# Power_grad2.net
KiCad netlist of a schematic drawn in EAGLE
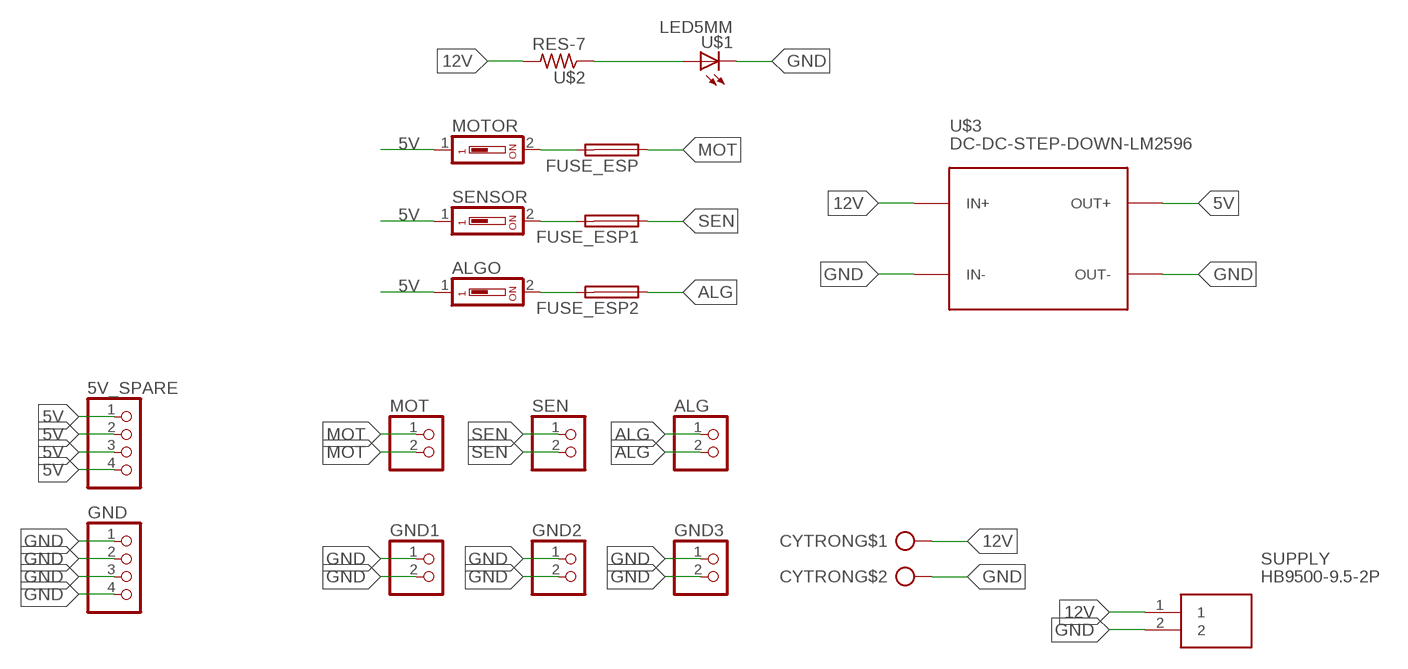
[diagram p0: schematic, sheet 1]

(export (version "E")
  (design (tool "Eeschema 10.0.6"))
  (components
    (comp (ref "5V_SPARE")
      (value "PINHD-1X4")
      (footprint "eagle-import:1X04")
      (libsource (lib "eagle-import") (part "PINHD-1X4"))
    )
    (comp (ref "ALG")
      (value "PINHD-2_DATA")
      (footprint "eagle-import:1X02_DATA")
      (libsource (lib "eagle-import") (part "PINHD-2_DATA"))
    )
    (comp (ref "ALGO")
      (value "DS01")
      (footprint "eagle-import:DS-01")
      (libsource (lib "eagle-import") (part "DS01"))
    )
    (comp (ref "CYTRON")
      (value "CON_PTR_2")
      (footprint "eagle-import:AK300_2")
      (libsource (lib "eagle-import") (part "CON_PTR_2"))
    )
    (comp (ref "FUSE_ESP")
      (value "FUSE_HOLDER")
      (footprint "eagle-import:SH22,5A")
      (libsource (lib "eagle-import") (part "FUSE_HOLDER"))
    )
    (comp (ref "FUSE_ESP1")
      (value "FUSE_HOLDER")
      (footprint "eagle-import:SH22,5A")
      (libsource (lib "eagle-import") (part "FUSE_HOLDER"))
    )
    (comp (ref "FUSE_ESP2")
      (value "FUSE_HOLDER")
      (footprint "eagle-import:SH22,5A")
      (libsource (lib "eagle-import") (part "FUSE_HOLDER"))
    )
    (comp (ref "GND")
      (value "PINHD-1X4")
      (footprint "eagle-import:1X04")
      (libsource (lib "eagle-import") (part "PINHD-1X4"))
    )
    (comp (ref "GND1")
      (value "PINHD-2_DATA")
      (footprint "eagle-import:1X02_DATA")
      (libsource (lib "eagle-import") (part "PINHD-2_DATA"))
    )
    (comp (ref "GND2")
      (value "PINHD-2_DATA")
      (footprint "eagle-import:1X02_DATA")
      (libsource (lib "eagle-import") (part "PINHD-2_DATA"))
    )
    (comp (ref "GND3")
      (value "PINHD-2_DATA")
      (footprint "eagle-import:1X02_DATA")
      (libsource (lib "eagle-import") (part "PINHD-2_DATA"))
    )
    (comp (ref "MOT")
      (value "PINHD-2_DATA")
      (footprint "eagle-import:1X02_DATA")
      (libsource (lib "eagle-import") (part "PINHD-2_DATA"))
    )
    (comp (ref "MOTOR")
      (value "DS01")
      (footprint "eagle-import:DS-01")
      (libsource (lib "eagle-import") (part "DS01"))
    )
    (comp (ref "SEN")
      (value "PINHD-2_DATA")
      (footprint "eagle-import:1X02_DATA")
      (libsource (lib "eagle-import") (part "PINHD-2_DATA"))
    )
    (comp (ref "SENSOR")
      (value "DS01")
      (footprint "eagle-import:DS-01")
      (libsource (lib "eagle-import") (part "DS01"))
    )
    (comp (ref "SUPPLY")
      (value "HB9500-9.5-2P")
      (footprint "eagle-import:SHDR2W140P0X950_1X2_2055X1800X")
      (libsource (lib "eagle-import") (part "HB9500-9.5-2P"))
    )
    (comp (ref "U$1")
      (value "LED5MM")
      (footprint "eagle-import:LED5MM")
      (libsource (lib "eagle-import") (part "LED5MM"))
    )
    (comp (ref "U$2")
      (value "RES-7")
      (footprint "eagle-import:0204_7")
      (libsource (lib "eagle-import") (part "RES-7"))
    )
    (comp (ref "U$3")
      (value "DC-DC-STEP-DOWN-LM2596")
      (footprint "eagle-import:DC-DC-STEP-DOWN-LM2596")
      (libsource (lib "eagle-import") (part "DC-DC-STEP-DOWN-LM2596"))
    )
  )
  (nets
    (net (code "1") (name "5V") (class "Default")
      (node (ref "5V_SPARE") (pin "1") (pinfunction "1_1") (pintype "passive"))
      (node (ref "5V_SPARE") (pin "2") (pinfunction "2_2") (pintype "passive"))
      (node (ref "5V_SPARE") (pin "3") (pinfunction "3_3") (pintype "passive"))
      (node (ref "5V_SPARE") (pin "4") (pinfunction "4_4") (pintype "passive"))
      (node (ref "ALGO") (pin "1") (pinfunction "1_1") (pintype "passive"))
      (node (ref "MOTOR") (pin "1") (pinfunction "1_1") (pintype "passive"))
      (node (ref "SENSOR") (pin "1") (pinfunction "1_1") (pintype "passive"))
      (node (ref "U$3") (pin "OUT+") (pinfunction "OUT+_OUT+") (pintype "bidirectional"))
    )
    (net (code "2") (name "12V") (class "Default")
      (node (ref "CYTRON") (pin "1") (pinfunction "KL_1") (pintype "passive"))
      (node (ref "SUPPLY") (pin "1") (pinfunction "1_1") (pintype "bidirectional"))
      (node (ref "U$2") (pin "2") (pinfunction "2_2") (pintype "passive"))
      (node (ref "U$3") (pin "IN+") (pinfunction "IN+_IN+") (pintype "bidirectional"))
    )
    (net (code "3") (name "ALG") (class "Default")
      (node (ref "ALG") (pin "1") (pinfunction "1_1") (pintype "passive"))
      (node (ref "ALG") (pin "2") (pinfunction "2_2") (pintype "passive"))
      (node (ref "FUSE_ESP2") (pin "1") (pinfunction "1_1") (pintype "passive"))
    )
    (net (code "4") (name "GND") (class "Default")
      (node (ref "CYTRON") (pin "2") (pinfunction "KL_2") (pintype "passive"))
      (node (ref "GND") (pin "1") (pinfunction "1_1") (pintype "passive"))
      (node (ref "GND") (pin "2") (pinfunction "2_2") (pintype "passive"))
      (node (ref "GND") (pin "3") (pinfunction "3_3") (pintype "passive"))
      (node (ref "GND") (pin "4") (pinfunction "4_4") (pintype "passive"))
      (node (ref "GND1") (pin "1") (pinfunction "1_1") (pintype "passive"))
      (node (ref "GND1") (pin "2") (pinfunction "2_2") (pintype "passive"))
      (node (ref "GND2") (pin "1") (pinfunction "1_1") (pintype "passive"))
      (node (ref "GND2") (pin "2") (pinfunction "2_2") (pintype "passive"))
      (node (ref "GND3") (pin "1") (pinfunction "1_1") (pintype "passive"))
      (node (ref "GND3") (pin "2") (pinfunction "2_2") (pintype "passive"))
      (node (ref "SUPPLY") (pin "2") (pinfunction "2_2") (pintype "bidirectional"))
      (node (ref "U$1") (pin "K") (pinfunction "C_K") (pintype "passive"))
      (node (ref "U$3") (pin "IN-") (pinfunction "IN-_IN-") (pintype "bidirectional"))
      (node (ref "U$3") (pin "OUT-") (pinfunction "OUT-_OUT-") (pintype "bidirectional"))
    )
    (net (code "5") (name "MOT") (class "Default")
      (node (ref "FUSE_ESP") (pin "1") (pinfunction "1_1") (pintype "passive"))
      (node (ref "MOT") (pin "1") (pinfunction "1_1") (pintype "passive"))
      (node (ref "MOT") (pin "2") (pinfunction "2_2") (pintype "passive"))
    )
    (net (code "6") (name "Net-(ALGO-Pad2)") (class "Default")
      (node (ref "ALGO") (pin "2") (pinfunction "2_2") (pintype "passive"))
      (node (ref "FUSE_ESP2") (pin "2") (pinfunction "2_2") (pintype "passive"))
    )
    (net (code "7") (name "Net-(FUSE_ESP-Pad2)") (class "Default")
      (node (ref "FUSE_ESP") (pin "2") (pinfunction "2_2") (pintype "passive"))
      (node (ref "MOTOR") (pin "2") (pinfunction "2_2") (pintype "passive"))
    )
    (net (code "8") (name "Net-(FUSE_ESP1-Pad2)") (class "Default")
      (node (ref "FUSE_ESP1") (pin "2") (pinfunction "2_2") (pintype "passive"))
      (node (ref "SENSOR") (pin "2") (pinfunction "2_2") (pintype "passive"))
    )
    (net (code "9") (name "Net-(U$1-PadA)") (class "Default")
      (node (ref "U$1") (pin "A") (pinfunction "A_A") (pintype "passive"))
      (node (ref "U$2") (pin "1") (pinfunction "1_1") (pintype "passive"))
    )
    (net (code "10") (name "SEN") (class "Default")
      (node (ref "FUSE_ESP1") (pin "1") (pinfunction "1_1") (pintype "passive"))
      (node (ref "SEN") (pin "1") (pinfunction "1_1") (pintype "passive"))
      (node (ref "SEN") (pin "2") (pinfunction "2_2") (pintype "passive"))
    )
  )
)
